# senseBox-OLED_v20.net
KiCad netlist of a schematic drawn in EAGLE
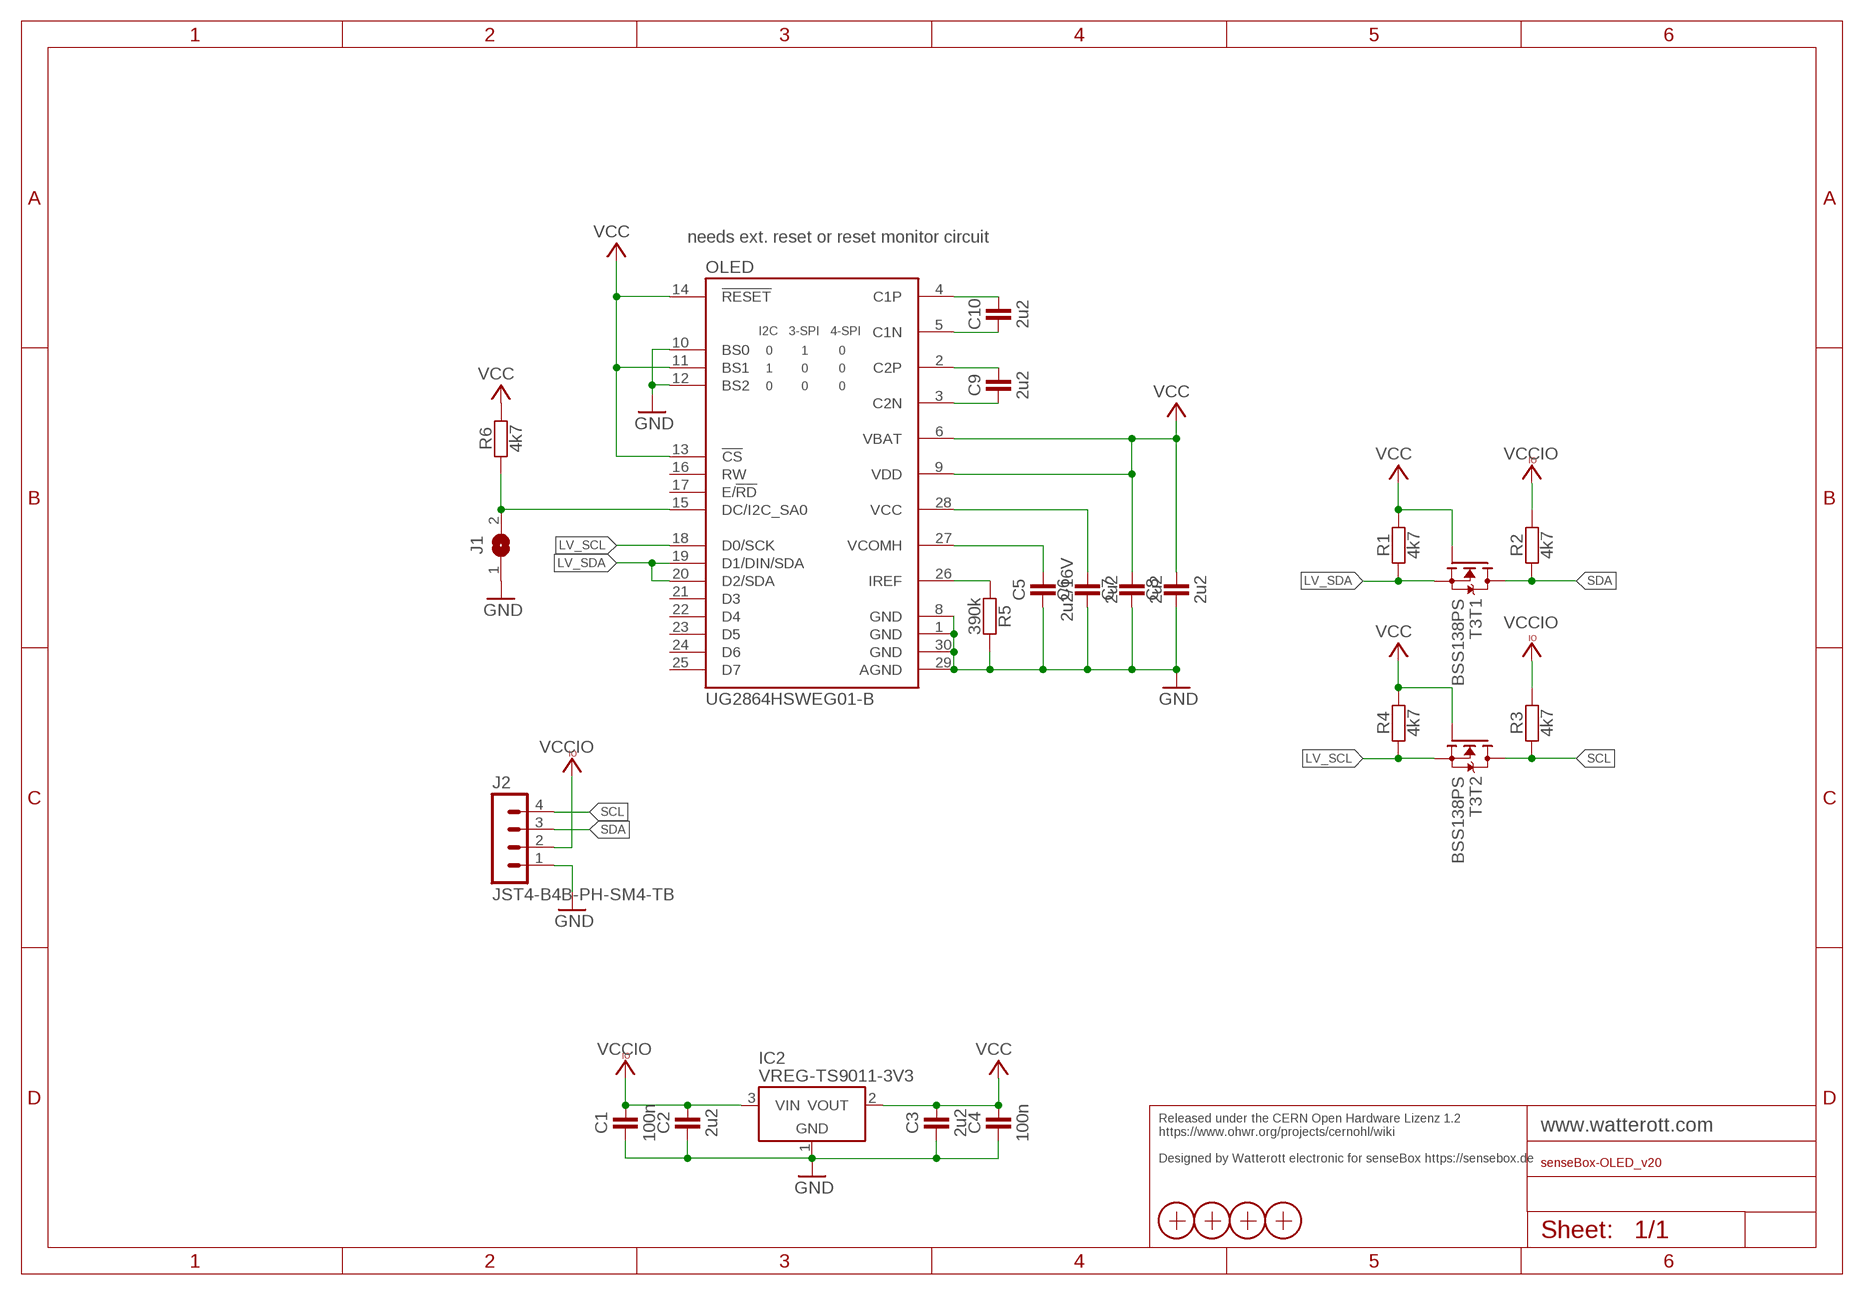
[diagram p0: schematic, sheet 1]

(export (version "E")
  (design (tool "Eeschema 10.0.6"))
  (components
    (comp (ref "C1")
      (value "100n")
      (footprint "eagle-import:C0402")
      (libsource (lib "eagle-import") (part "CAPACITOR-0402"))
    )
    (comp (ref "C2")
      (value "2u2")
      (footprint "eagle-import:C0402")
      (libsource (lib "eagle-import") (part "CAPACITOR-0402"))
    )
    (comp (ref "C3")
      (value "2u2")
      (footprint "eagle-import:C0402")
      (libsource (lib "eagle-import") (part "CAPACITOR-0402"))
    )
    (comp (ref "C4")
      (value "100n")
      (footprint "eagle-import:C0402")
      (libsource (lib "eagle-import") (part "CAPACITOR-0402"))
    )
    (comp (ref "C5")
      (value "2u2/16V")
      (footprint "eagle-import:C0402")
      (libsource (lib "eagle-import") (part "CAPACITOR-0402"))
    )
    (comp (ref "C6")
      (value "2u2")
      (footprint "eagle-import:C0402")
      (libsource (lib "eagle-import") (part "CAPACITOR-0402"))
    )
    (comp (ref "C7")
      (value "2u2")
      (footprint "eagle-import:C0402")
      (libsource (lib "eagle-import") (part "CAPACITOR-0402"))
    )
    (comp (ref "C8")
      (value "2u2")
      (footprint "eagle-import:C0402")
      (libsource (lib "eagle-import") (part "CAPACITOR-0402"))
    )
    (comp (ref "C9")
      (value "2u2")
      (footprint "eagle-import:C0402")
      (libsource (lib "eagle-import") (part "CAPACITOR-0402"))
    )
    (comp (ref "C10")
      (value "2u2")
      (footprint "eagle-import:C0402")
      (libsource (lib "eagle-import") (part "CAPACITOR-0402"))
    )
    (comp (ref "IC2")
      (value "VREG-TS9011-3V3")
      (footprint "eagle-import:SOT23")
      (libsource (lib "eagle-import") (part "VREG-TS9011-3V3"))
    )
    (comp (ref "J1")
      (value "JUMPER2-0402-NC")
      (footprint "eagle-import:JUMPER2-0402_NC")
      (libsource (lib "eagle-import") (part "JUMPER2-0402-NC"))
    )
    (comp (ref "J2")
      (value "JST4-B4B-PH-SM4-TB")
      (footprint "eagle-import:JST_B4B-PH-SM4-TB")
      (libsource (lib "eagle-import") (part "JST4-B4B-PH-SM4-TB"))
    )
    (comp (ref "OLED")
      (value "UG2864HSWEG01-B")
      (footprint "eagle-import:UG2864HSWEG01_BOT")
      (libsource (lib "eagle-import") (part "UG2864HSWEG01-B"))
    )
    (comp (ref "R1")
      (value "4k7")
      (footprint "eagle-import:C0402")
      (libsource (lib "eagle-import") (part "RESISTOR-0402"))
    )
    (comp (ref "R2")
      (value "4k7")
      (footprint "eagle-import:C0402")
      (libsource (lib "eagle-import") (part "RESISTOR-0402"))
    )
    (comp (ref "R3")
      (value "4k7")
      (footprint "eagle-import:C0402")
      (libsource (lib "eagle-import") (part "RESISTOR-0402"))
    )
    (comp (ref "R4")
      (value "4k7")
      (footprint "eagle-import:C0402")
      (libsource (lib "eagle-import") (part "RESISTOR-0402"))
    )
    (comp (ref "R5")
      (value "390k")
      (footprint "eagle-import:C0402")
      (libsource (lib "eagle-import") (part "RESISTOR-0402"))
    )
    (comp (ref "R6")
      (value "4k7")
      (footprint "eagle-import:C0402")
      (libsource (lib "eagle-import") (part "RESISTOR-0402"))
    )
    (comp (ref "T3")
      (value "BSS138PS")
      (footprint "eagle-import:SOT363")
      (libsource (lib "eagle-import") (part "BSS138PS"))
    )
    (comp (ref "X1")
      (value "PASSER-07")
      (footprint "eagle-import:PASSER_07MM")
      (libsource (lib "eagle-import") (part "PASSER-07"))
    )
    (comp (ref "X2")
      (value "PASSER-07")
      (footprint "eagle-import:PASSER_07MM")
      (libsource (lib "eagle-import") (part "PASSER-07"))
    )
    (comp (ref "X3")
      (value "PASSER-07")
      (footprint "eagle-import:PASSER_07MM")
      (libsource (lib "eagle-import") (part "PASSER-07"))
    )
    (comp (ref "X4")
      (value "PASSER-07")
      (footprint "eagle-import:PASSER_07MM")
      (libsource (lib "eagle-import") (part "PASSER-07"))
    )
  )
  (nets
    (net (code "1") (name "GND") (class "Default")
      (node (ref "C1") (pin "1") (pinfunction "1_1") (pintype "passive"))
      (node (ref "C2") (pin "1") (pinfunction "1_1") (pintype "passive"))
      (node (ref "C3") (pin "1") (pinfunction "1_1") (pintype "passive"))
      (node (ref "C4") (pin "1") (pinfunction "1_1") (pintype "passive"))
      (node (ref "C5") (pin "1") (pinfunction "1_1") (pintype "passive"))
      (node (ref "C6") (pin "1") (pinfunction "1_1") (pintype "passive"))
      (node (ref "C7") (pin "1") (pinfunction "1_1") (pintype "passive"))
      (node (ref "C8") (pin "1") (pinfunction "1_1") (pintype "passive"))
      (node (ref "IC2") (pin "1") (pinfunction "GND_1") (pintype "power_in"))
      (node (ref "J1") (pin "1") (pinfunction "1_1") (pintype "passive"))
      (node (ref "J2") (pin "1") (pinfunction "1_1") (pintype "passive"))
      (node (ref "OLED") (pin "1") (pinfunction "GND_1") (pintype "power_in"))
      (node (ref "OLED") (pin "10") (pinfunction "BS0_10") (pintype "input"))
      (node (ref "OLED") (pin "12") (pinfunction "BS2_12") (pintype "input"))
      (node (ref "OLED") (pin "29") (pinfunction "AGND_29") (pintype "power_in"))
      (node (ref "OLED") (pin "30") (pinfunction "GND_30") (pintype "power_in"))
      (node (ref "OLED") (pin "8") (pinfunction "GND_8") (pintype "power_in"))
      (node (ref "R5") (pin "2") (pinfunction "2_2") (pintype "passive"))
    )
    (net (code "2") (name "LV_SCL") (class "Default")
      (node (ref "OLED") (pin "18") (pinfunction "D0/SCK_18") (pintype "bidirectional"))
      (node (ref "R4") (pin "1") (pinfunction "1_1") (pintype "passive"))
      (node (ref "T3") (pin "4") (pinfunction "S_4") (pintype "passive"))
    )
    (net (code "3") (name "LV_SDA") (class "Default")
      (node (ref "OLED") (pin "19") (pinfunction "D1/DIN/SDA_19") (pintype "bidirectional"))
      (node (ref "OLED") (pin "20") (pinfunction "D2/SDA_20") (pintype "bidirectional"))
      (node (ref "R1") (pin "1") (pinfunction "1_1") (pintype "passive"))
      (node (ref "T3") (pin "1") (pinfunction "S_1") (pintype "passive"))
    )
    (net (code "4") (name "Net-(OLED-C1N)") (class "Default")
      (node (ref "C10") (pin "1") (pinfunction "1_1") (pintype "passive"))
      (node (ref "OLED") (pin "5") (pinfunction "C1N_5") (pintype "passive"))
    )
    (net (code "5") (name "Net-(OLED-C1P)") (class "Default")
      (node (ref "C10") (pin "2") (pinfunction "2_2") (pintype "passive"))
      (node (ref "OLED") (pin "4") (pinfunction "C1P_4") (pintype "passive"))
    )
    (net (code "6") (name "Net-(OLED-C2N)") (class "Default")
      (node (ref "C9") (pin "1") (pinfunction "1_1") (pintype "passive"))
      (node (ref "OLED") (pin "3") (pinfunction "C2N_3") (pintype "passive"))
    )
    (net (code "7") (name "Net-(OLED-C2P)") (class "Default")
      (node (ref "C9") (pin "2") (pinfunction "2_2") (pintype "passive"))
      (node (ref "OLED") (pin "2") (pinfunction "C2P_2") (pintype "passive"))
    )
    (net (code "8") (name "Net-(OLED-DC{slash}I2C_SA0)") (class "Default")
      (node (ref "J1") (pin "2") (pinfunction "2_2") (pintype "passive"))
      (node (ref "OLED") (pin "15") (pinfunction "DC/I2C_SA0_15") (pintype "input"))
      (node (ref "R6") (pin "1") (pinfunction "1_1") (pintype "passive"))
    )
    (net (code "9") (name "Net-(OLED-IREF)") (class "Default")
      (node (ref "OLED") (pin "26") (pinfunction "IREF_26") (pintype "passive"))
      (node (ref "R5") (pin "1") (pinfunction "1_1") (pintype "passive"))
    )
    (net (code "10") (name "Net-(OLED-VCC)") (class "Default")
      (node (ref "C6") (pin "2") (pinfunction "2_2") (pintype "passive"))
      (node (ref "OLED") (pin "28") (pinfunction "VCC_28") (pintype "power_in"))
    )
    (net (code "11") (name "Net-(OLED-VCOMH)") (class "Default")
      (node (ref "C5") (pin "2") (pinfunction "2_2") (pintype "passive"))
      (node (ref "OLED") (pin "27") (pinfunction "VCOMH_27") (pintype "power_in"))
    )
    (net (code "12") (name "SCL") (class "Default")
      (node (ref "J2") (pin "4") (pinfunction "4_4") (pintype "passive"))
      (node (ref "R3") (pin "1") (pinfunction "1_1") (pintype "passive"))
      (node (ref "T3") (pin "3") (pinfunction "D_3") (pintype "passive"))
    )
    (net (code "13") (name "SDA") (class "Default")
      (node (ref "J2") (pin "3") (pinfunction "3_3") (pintype "passive"))
      (node (ref "R2") (pin "1") (pinfunction "1_1") (pintype "passive"))
      (node (ref "T3") (pin "6") (pinfunction "D_6") (pintype "passive"))
    )
    (net (code "14") (name "VCC") (class "Default")
      (node (ref "C3") (pin "2") (pinfunction "2_2") (pintype "passive"))
      (node (ref "C4") (pin "2") (pinfunction "2_2") (pintype "passive"))
      (node (ref "C7") (pin "2") (pinfunction "2_2") (pintype "passive"))
      (node (ref "C8") (pin "2") (pinfunction "2_2") (pintype "passive"))
      (node (ref "IC2") (pin "2") (pinfunction "VOUT_2") (pintype "power_in"))
      (node (ref "OLED") (pin "11") (pinfunction "BS1_11") (pintype "input"))
      (node (ref "OLED") (pin "13") (pinfunction "~{CS}_13") (pintype "input"))
      (node (ref "OLED") (pin "14") (pinfunction "~{RESET}_14") (pintype "input"))
      (node (ref "OLED") (pin "6") (pinfunction "VBAT_6") (pintype "power_in"))
      (node (ref "OLED") (pin "9") (pinfunction "VDD_9") (pintype "power_in"))
      (node (ref "R1") (pin "2") (pinfunction "2_2") (pintype "passive"))
      (node (ref "R4") (pin "2") (pinfunction "2_2") (pintype "passive"))
      (node (ref "R6") (pin "2") (pinfunction "2_2") (pintype "passive"))
      (node (ref "T3") (pin "2") (pinfunction "G_2") (pintype "passive"))
      (node (ref "T3") (pin "5") (pinfunction "G_5") (pintype "passive"))
    )
    (net (code "15") (name "VCCIO") (class "Default")
      (node (ref "C1") (pin "2") (pinfunction "2_2") (pintype "passive"))
      (node (ref "C2") (pin "2") (pinfunction "2_2") (pintype "passive"))
      (node (ref "IC2") (pin "3") (pinfunction "VIN_3") (pintype "power_in"))
      (node (ref "J2") (pin "2") (pinfunction "2_2") (pintype "passive"))
      (node (ref "R2") (pin "2") (pinfunction "2_2") (pintype "passive"))
      (node (ref "R3") (pin "2") (pinfunction "2_2") (pintype "passive"))
    )
    (net (code "16") (name "unconnected-(OLED-D3-Pad21)") (class "Default")
      (node (ref "OLED") (pin "21") (pinfunction "D3_21") (pintype "bidirectional"))
    )
    (net (code "17") (name "unconnected-(OLED-D4-Pad22)") (class "Default")
      (node (ref "OLED") (pin "22") (pinfunction "D4_22") (pintype "bidirectional"))
    )
    (net (code "18") (name "unconnected-(OLED-D5-Pad23)") (class "Default")
      (node (ref "OLED") (pin "23") (pinfunction "D5_23") (pintype "bidirectional"))
    )
    (net (code "19") (name "unconnected-(OLED-D6-Pad24)") (class "Default")
      (node (ref "OLED") (pin "24") (pinfunction "D6_24") (pintype "bidirectional"))
    )
    (net (code "20") (name "unconnected-(OLED-D7-Pad25)") (class "Default")
      (node (ref "OLED") (pin "25") (pinfunction "D7_25") (pintype "bidirectional"))
    )
    (net (code "21") (name "unconnected-(OLED-E{slash}~{RD}-Pad17)") (class "Default")
      (node (ref "OLED") (pin "17") (pinfunction "E/~{RD}_17") (pintype "bidirectional"))
    )
    (net (code "22") (name "unconnected-(OLED-RW-Pad16)") (class "Default")
      (node (ref "OLED") (pin "16") (pinfunction "RW_16") (pintype "bidirectional"))
    )
  )
)
